# ArdLedRing.net
KiCad netlist of a schematic drawn in EAGLE
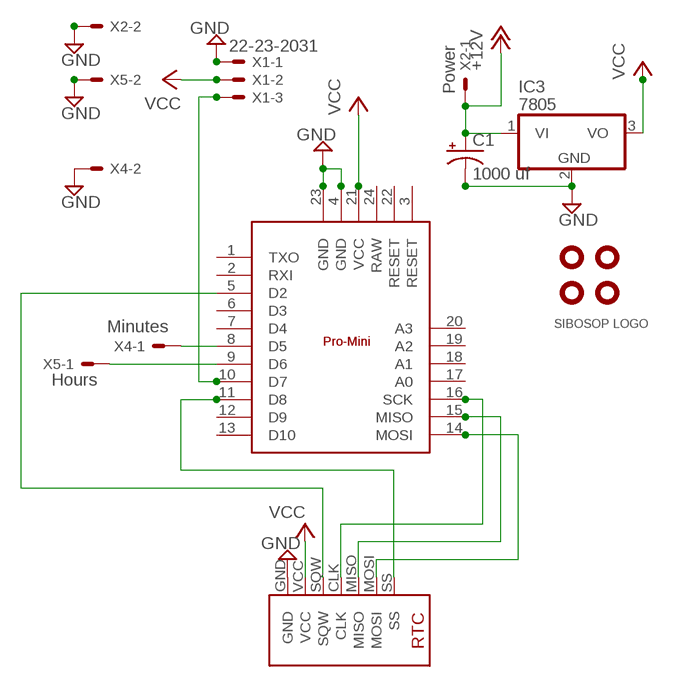
[diagram p0: schematic, sheet 1]

(export (version "E")
  (design (tool "Eeschema 10.0.6"))
  (components
    (comp (ref "C1")
      (value "1000 uf")
      (footprint "eagle-import:E3,5-10")
      (libsource (lib "eagle-import") (part "CPOL-USE3.5-10"))
    )
    (comp (ref "IC1")
      (value "PRO-MINI")
      (footprint "eagle-import:DIL24-6-EXT")
      (libsource (lib "eagle-import") (part "PRO-MINI"))
    )
    (comp (ref "IC2")
      (value "SPARKRTC")
      (footprint "eagle-import:SPARKRTC")
      (libsource (lib "eagle-import") (part "SPARKRTC"))
    )
    (comp (ref "IC3")
      (value "7805")
      (footprint "eagle-import:TO220V")
      (libsource (lib "eagle-import") (part "7805"))
    )
    (comp (ref "U$1")
      (value "LOGO")
      (footprint "eagle-import:LOGO")
      (libsource (lib "eagle-import") (part "LOGO"))
    )
    (comp (ref "U$2")
      (value "HOLE-125")
      (footprint "eagle-import:HOLE-125")
      (libsource (lib "eagle-import") (part "HOLE-125"))
    )
    (comp (ref "U$3")
      (value "HOLE-125")
      (footprint "eagle-import:HOLE-125")
      (libsource (lib "eagle-import") (part "HOLE-125"))
    )
    (comp (ref "U$4")
      (value "HOLE-125")
      (footprint "eagle-import:HOLE-125")
      (libsource (lib "eagle-import") (part "HOLE-125"))
    )
    (comp (ref "U$5")
      (value "HOLE-125")
      (footprint "eagle-import:HOLE-125")
      (libsource (lib "eagle-import") (part "HOLE-125"))
    )
    (comp (ref "X1")
      (value "22-23-2031")
      (footprint "eagle-import:22-23-2031")
      (libsource (lib "eagle-import") (part "22-23-2031"))
    )
    (comp (ref "X2")
      (value "Power")
      (footprint "eagle-import:22-23-2021")
      (libsource (lib "eagle-import") (part "22-23-2021"))
    )
    (comp (ref "X4")
      (value "Minutes")
      (footprint "eagle-import:22-23-2021")
      (libsource (lib "eagle-import") (part "22-23-2021"))
    )
    (comp (ref "X5")
      (value "Hours")
      (footprint "eagle-import:22-23-2021")
      (libsource (lib "eagle-import") (part "22-23-2021"))
    )
  )
  (nets
    (net (code "1") (name "+12V") (class "Default")
      (node (ref "C1") (pin "+") (pinfunction "+_+") (pintype "passive"))
      (node (ref "IC3") (pin "1") (pinfunction "VI_1") (pintype "input"))
      (node (ref "X2") (pin "1") (pinfunction "S_1") (pintype "passive"))
    )
    (net (code "2") (name "/RAW") (class "Default")
      (node (ref "IC1") (pin "24") (pinfunction "RAW_24") (pintype "power_in"))
    )
    (net (code "3") (name "GND") (class "Default")
      (node (ref "C1") (pin "-") (pinfunction "-_-") (pintype "passive"))
      (node (ref "IC1") (pin "23") (pinfunction "GND_23") (pintype "bidirectional"))
      (node (ref "IC1") (pin "4") (pinfunction "GND_4") (pintype "power_in"))
      (node (ref "IC2") (pin "GND") (pinfunction "GND_GND") (pintype "power_in"))
      (node (ref "IC3") (pin "2") (pinfunction "GND_2") (pintype "passive"))
      (node (ref "X1") (pin "1") (pinfunction "S_1") (pintype "passive"))
      (node (ref "X2") (pin "2") (pinfunction "S_2") (pintype "passive"))
      (node (ref "X4") (pin "2") (pinfunction "S_2") (pintype "passive"))
      (node (ref "X5") (pin "2") (pinfunction "S_2") (pintype "passive"))
    )
    (net (code "4") (name "Net-(IC1-D2)") (class "Default")
      (node (ref "IC1") (pin "5") (pinfunction "D2_5") (pintype "bidirectional"))
      (node (ref "IC2") (pin "SQW") (pinfunction "SQW_SQW") (pintype "bidirectional"))
    )
    (net (code "5") (name "Net-(IC1-D5)") (class "Default")
      (node (ref "IC1") (pin "8") (pinfunction "D5_8") (pintype "bidirectional"))
      (node (ref "X4") (pin "1") (pinfunction "S_1") (pintype "passive"))
    )
    (net (code "6") (name "Net-(IC1-D6)") (class "Default")
      (node (ref "IC1") (pin "9") (pinfunction "D6_9") (pintype "bidirectional"))
      (node (ref "X5") (pin "1") (pinfunction "S_1") (pintype "passive"))
    )
    (net (code "7") (name "Net-(IC1-D7)") (class "Default")
      (node (ref "IC1") (pin "10") (pinfunction "D7_10") (pintype "bidirectional"))
      (node (ref "X1") (pin "3") (pinfunction "S_3") (pintype "passive"))
    )
    (net (code "8") (name "Net-(IC1-D8)") (class "Default")
      (node (ref "IC1") (pin "11") (pinfunction "D8_11") (pintype "bidirectional"))
      (node (ref "IC2") (pin "SS") (pinfunction "SS_SS") (pintype "bidirectional"))
    )
    (net (code "9") (name "Net-(IC1-MISO)") (class "Default")
      (node (ref "IC1") (pin "15") (pinfunction "MISO_15") (pintype "bidirectional"))
      (node (ref "IC2") (pin "MISO") (pinfunction "MISO_MISO") (pintype "bidirectional"))
    )
    (net (code "10") (name "Net-(IC1-MOSI)") (class "Default")
      (node (ref "IC1") (pin "14") (pinfunction "MOSI_14") (pintype "bidirectional"))
      (node (ref "IC2") (pin "MOSI") (pinfunction "MOSI_MOSI") (pintype "bidirectional"))
    )
    (net (code "11") (name "Net-(IC1-SCK)") (class "Default")
      (node (ref "IC1") (pin "16") (pinfunction "SCK_16") (pintype "bidirectional"))
      (node (ref "IC2") (pin "CLK") (pinfunction "CLK_CLK") (pintype "bidirectional"))
    )
    (net (code "12") (name "VCC") (class "Default")
      (node (ref "IC1") (pin "21") (pinfunction "VCC_21") (pintype "power_in"))
      (node (ref "IC2") (pin "VCC") (pinfunction "VCC_VCC") (pintype "power_in"))
      (node (ref "IC3") (pin "3") (pinfunction "VO_3") (pintype "passive"))
      (node (ref "X1") (pin "2") (pinfunction "S_2") (pintype "passive"))
    )
    (net (code "13") (name "unconnected-(IC1-A0-Pad17)") (class "Default")
      (node (ref "IC1") (pin "17") (pinfunction "A0_17") (pintype "bidirectional"))
    )
    (net (code "14") (name "unconnected-(IC1-A1-Pad18)") (class "Default")
      (node (ref "IC1") (pin "18") (pinfunction "A1_18") (pintype "bidirectional"))
    )
    (net (code "15") (name "unconnected-(IC1-A2-Pad19)") (class "Default")
      (node (ref "IC1") (pin "19") (pinfunction "A2_19") (pintype "bidirectional"))
    )
    (net (code "16") (name "unconnected-(IC1-A3-Pad20)") (class "Default")
      (node (ref "IC1") (pin "20") (pinfunction "A3_20") (pintype "bidirectional"))
    )
    (net (code "17") (name "unconnected-(IC1-D3-Pad6)") (class "Default")
      (node (ref "IC1") (pin "6") (pinfunction "D3_6") (pintype "bidirectional"))
    )
    (net (code "18") (name "unconnected-(IC1-D4-Pad7)") (class "Default")
      (node (ref "IC1") (pin "7") (pinfunction "D4_7") (pintype "bidirectional"))
    )
    (net (code "19") (name "unconnected-(IC1-D9-Pad12)") (class "Default")
      (node (ref "IC1") (pin "12") (pinfunction "D9_12") (pintype "bidirectional"))
    )
    (net (code "20") (name "unconnected-(IC1-D10-Pad13)") (class "Default")
      (node (ref "IC1") (pin "13") (pinfunction "D10_13") (pintype "bidirectional"))
    )
    (net (code "21") (name "unconnected-(IC1-RESET-Pad3)") (class "Default")
      (node (ref "IC1") (pin "3") (pinfunction "RESET_3") (pintype "input"))
    )
    (net (code "22") (name "unconnected-(IC1-RESET-Pad22)") (class "Default")
      (node (ref "IC1") (pin "22") (pinfunction "RESET_22") (pintype "bidirectional"))
    )
    (net (code "23") (name "unconnected-(IC1-RXI-Pad2)") (class "Default")
      (node (ref "IC1") (pin "2") (pinfunction "RXI_2") (pintype "input"))
    )
    (net (code "24") (name "unconnected-(IC1-TXO-Pad1)") (class "Default")
      (node (ref "IC1") (pin "1") (pinfunction "TXO_1") (pintype "output"))
    )
  )
)
